# expansion-w-power.net
KiCad netlist of a schematic drawn in EAGLE
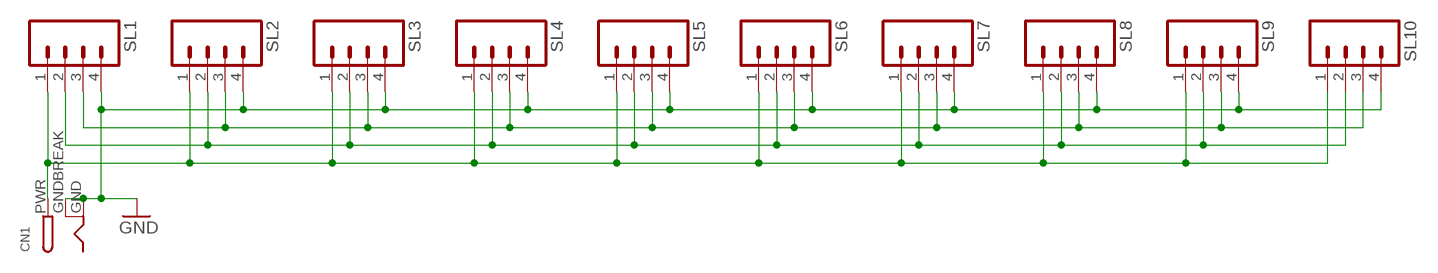
[diagram p0: schematic, sheet 1]

(export (version "E")
  (design (tool "Eeschema 10.0.6"))
  (components
    (comp (ref "CN1")
      (value "DCBARRELPTH")
      (footprint "eagle-import:DCJACK_2MM_PTH")
      (libsource (lib "eagle-import") (part "DCBARRELPTH"))
    )
    (comp (ref "SL1")
      (value "M04")
      (footprint "eagle-import:04P")
      (libsource (lib "eagle-import") (part "M04"))
    )
    (comp (ref "SL2")
      (value "M04")
      (footprint "eagle-import:04P")
      (libsource (lib "eagle-import") (part "M04"))
    )
    (comp (ref "SL3")
      (value "M04")
      (footprint "eagle-import:04P")
      (libsource (lib "eagle-import") (part "M04"))
    )
    (comp (ref "SL4")
      (value "M04")
      (footprint "eagle-import:04P")
      (libsource (lib "eagle-import") (part "M04"))
    )
    (comp (ref "SL5")
      (value "M04")
      (footprint "eagle-import:04P")
      (libsource (lib "eagle-import") (part "M04"))
    )
    (comp (ref "SL6")
      (value "M04")
      (footprint "eagle-import:04P")
      (libsource (lib "eagle-import") (part "M04"))
    )
    (comp (ref "SL7")
      (value "M04")
      (footprint "eagle-import:04P")
      (libsource (lib "eagle-import") (part "M04"))
    )
    (comp (ref "SL8")
      (value "M04")
      (footprint "eagle-import:04P")
      (libsource (lib "eagle-import") (part "M04"))
    )
    (comp (ref "SL9")
      (value "M04")
      (footprint "eagle-import:04P")
      (libsource (lib "eagle-import") (part "M04"))
    )
    (comp (ref "SL10")
      (value "M04")
      (footprint "eagle-import:04P")
      (libsource (lib "eagle-import") (part "M04"))
    )
  )
  (nets
    (net (code "1") (name "GND") (class "Default")
      (node (ref "CN1") (pin "GND") (pinfunction "GND_GND") (pintype "power_in"))
      (node (ref "CN1") (pin "GNDBREAK") (pinfunction "GNDBREAK_GNDBREAK") (pintype "power_in"))
      (node (ref "SL1") (pin "4") (pinfunction "4_4") (pintype "passive"))
      (node (ref "SL10") (pin "4") (pinfunction "4_4") (pintype "passive"))
      (node (ref "SL2") (pin "4") (pinfunction "4_4") (pintype "passive"))
      (node (ref "SL3") (pin "4") (pinfunction "4_4") (pintype "passive"))
      (node (ref "SL4") (pin "4") (pinfunction "4_4") (pintype "passive"))
      (node (ref "SL5") (pin "4") (pinfunction "4_4") (pintype "passive"))
      (node (ref "SL6") (pin "4") (pinfunction "4_4") (pintype "passive"))
      (node (ref "SL7") (pin "4") (pinfunction "4_4") (pintype "passive"))
      (node (ref "SL8") (pin "4") (pinfunction "4_4") (pintype "passive"))
      (node (ref "SL9") (pin "4") (pinfunction "4_4") (pintype "passive"))
    )
    (net (code "2") (name "Net-(CN1-PadPWR)") (class "Default")
      (node (ref "CN1") (pin "PWR") (pinfunction "PWR_PWR") (pintype "power_in"))
      (node (ref "SL1") (pin "1") (pinfunction "1_1") (pintype "passive"))
      (node (ref "SL10") (pin "1") (pinfunction "1_1") (pintype "passive"))
      (node (ref "SL2") (pin "1") (pinfunction "1_1") (pintype "passive"))
      (node (ref "SL3") (pin "1") (pinfunction "1_1") (pintype "passive"))
      (node (ref "SL4") (pin "1") (pinfunction "1_1") (pintype "passive"))
      (node (ref "SL5") (pin "1") (pinfunction "1_1") (pintype "passive"))
      (node (ref "SL6") (pin "1") (pinfunction "1_1") (pintype "passive"))
      (node (ref "SL7") (pin "1") (pinfunction "1_1") (pintype "passive"))
      (node (ref "SL8") (pin "1") (pinfunction "1_1") (pintype "passive"))
      (node (ref "SL9") (pin "1") (pinfunction "1_1") (pintype "passive"))
    )
    (net (code "3") (name "Net-(SL1-Pad2)") (class "Default")
      (node (ref "SL1") (pin "2") (pinfunction "2_2") (pintype "passive"))
      (node (ref "SL10") (pin "2") (pinfunction "2_2") (pintype "passive"))
      (node (ref "SL2") (pin "2") (pinfunction "2_2") (pintype "passive"))
      (node (ref "SL3") (pin "2") (pinfunction "2_2") (pintype "passive"))
      (node (ref "SL4") (pin "2") (pinfunction "2_2") (pintype "passive"))
      (node (ref "SL5") (pin "2") (pinfunction "2_2") (pintype "passive"))
      (node (ref "SL6") (pin "2") (pinfunction "2_2") (pintype "passive"))
      (node (ref "SL7") (pin "2") (pinfunction "2_2") (pintype "passive"))
      (node (ref "SL8") (pin "2") (pinfunction "2_2") (pintype "passive"))
      (node (ref "SL9") (pin "2") (pinfunction "2_2") (pintype "passive"))
    )
    (net (code "4") (name "Net-(SL1-Pad3)") (class "Default")
      (node (ref "SL1") (pin "3") (pinfunction "3_3") (pintype "passive"))
      (node (ref "SL10") (pin "3") (pinfunction "3_3") (pintype "passive"))
      (node (ref "SL2") (pin "3") (pinfunction "3_3") (pintype "passive"))
      (node (ref "SL3") (pin "3") (pinfunction "3_3") (pintype "passive"))
      (node (ref "SL4") (pin "3") (pinfunction "3_3") (pintype "passive"))
      (node (ref "SL5") (pin "3") (pinfunction "3_3") (pintype "passive"))
      (node (ref "SL6") (pin "3") (pinfunction "3_3") (pintype "passive"))
      (node (ref "SL7") (pin "3") (pinfunction "3_3") (pintype "passive"))
      (node (ref "SL8") (pin "3") (pinfunction "3_3") (pintype "passive"))
      (node (ref "SL9") (pin "3") (pinfunction "3_3") (pintype "passive"))
    )
  )
)
